# Connector_Board.net
KiCad netlist of a schematic drawn in EAGLE
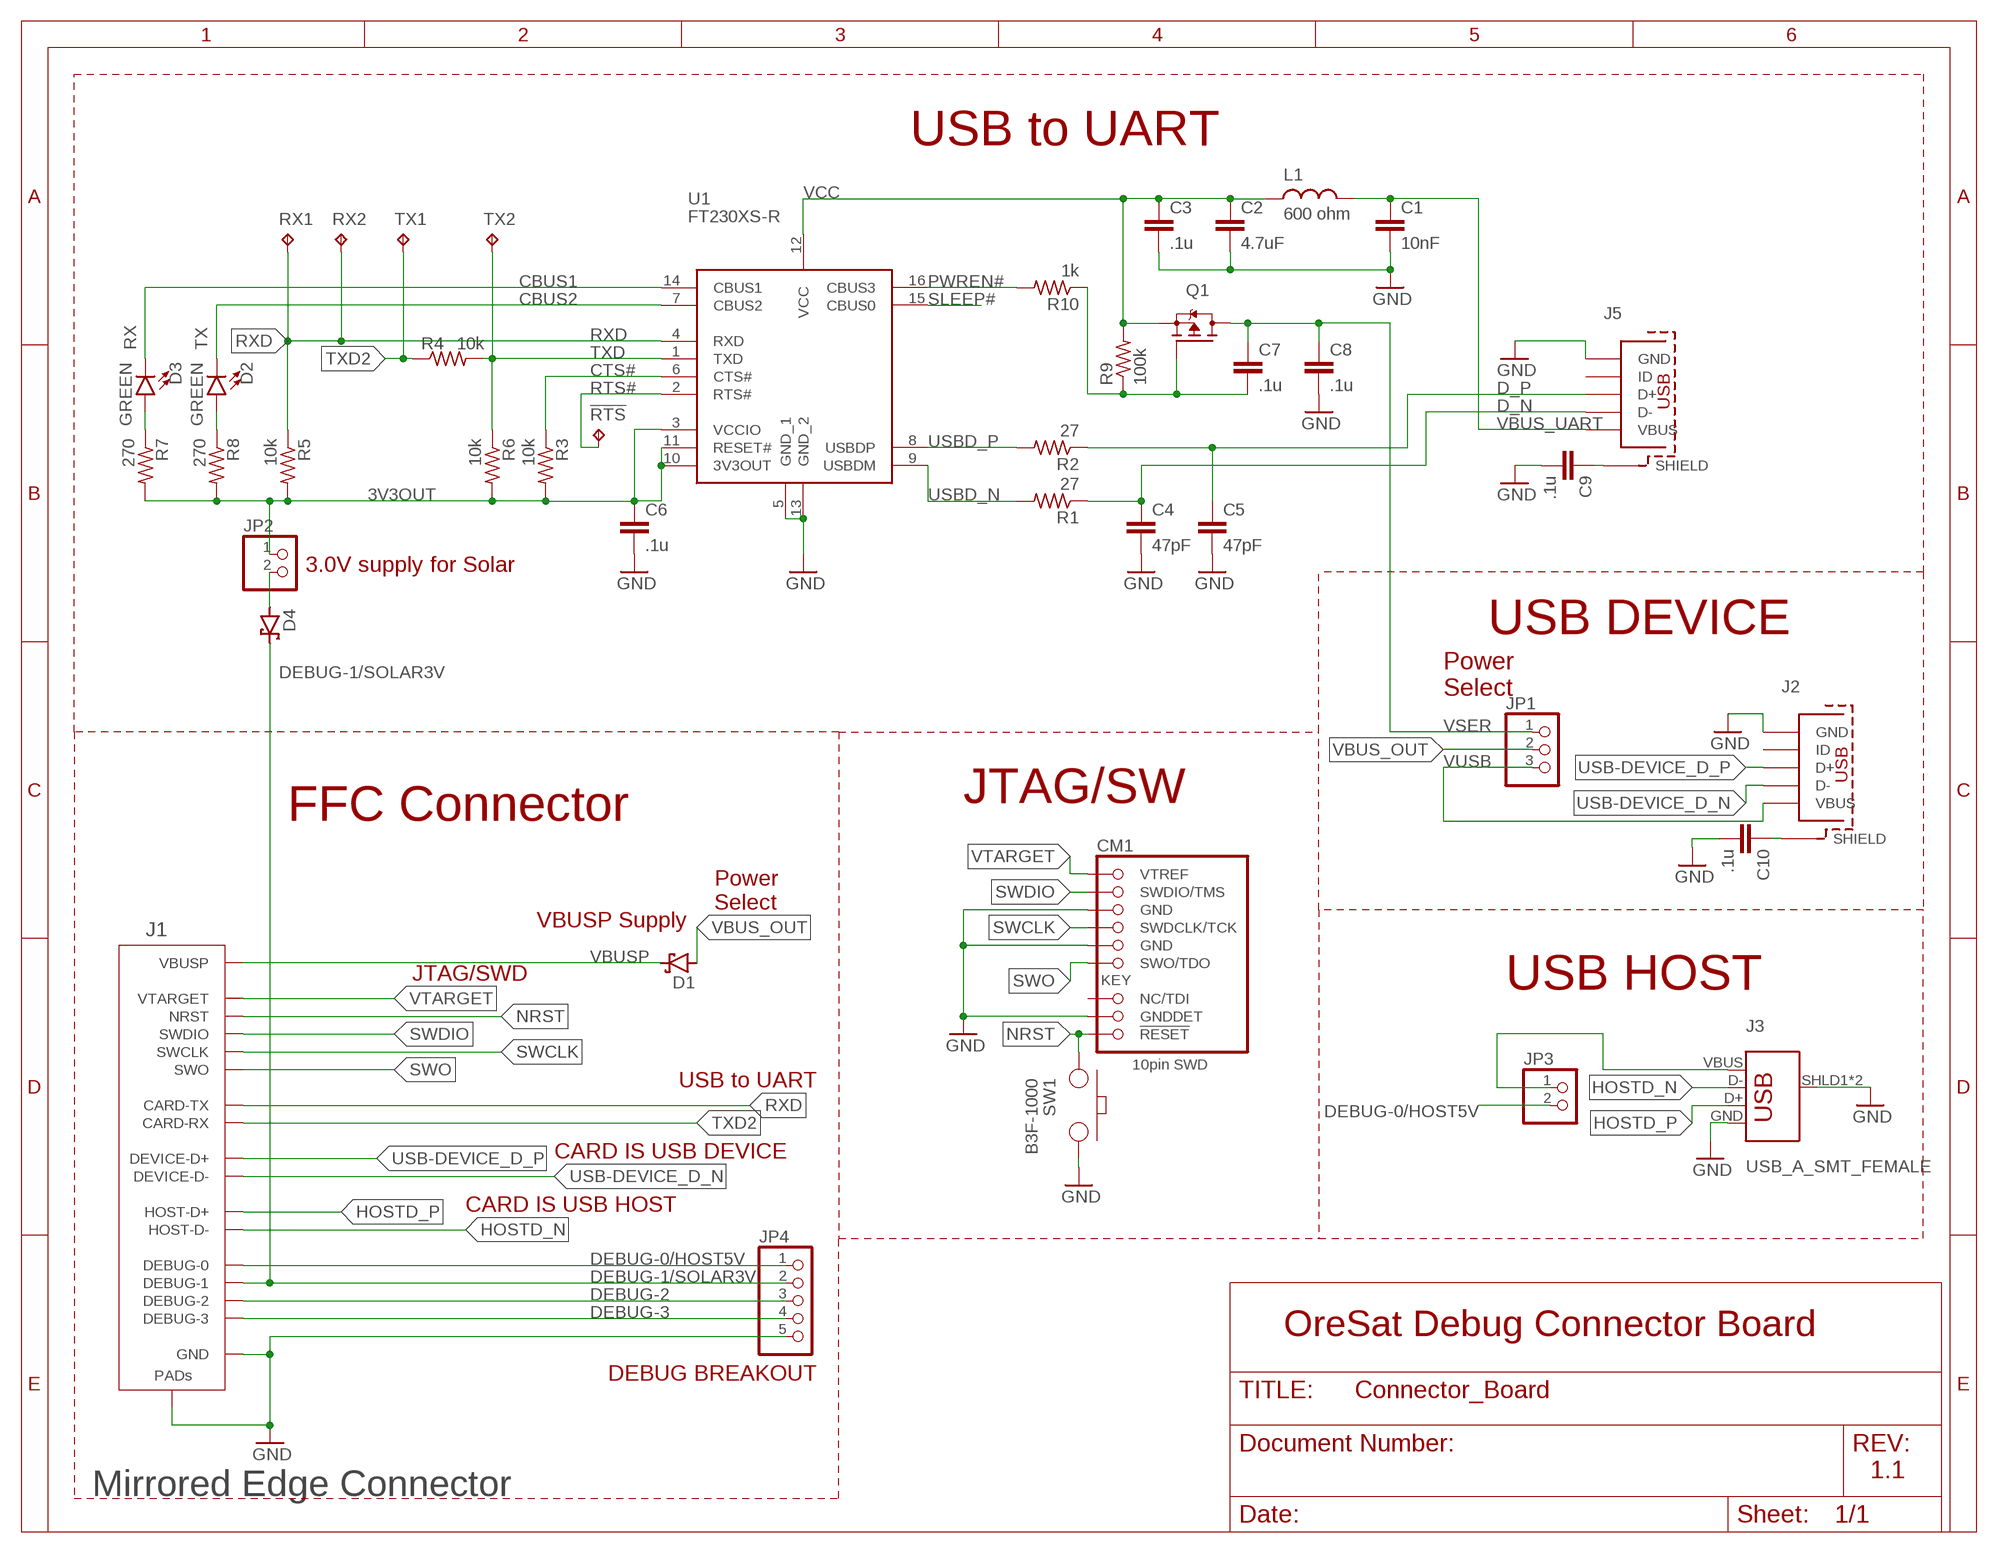
[diagram p0: schematic, sheet 1]

(export (version "E")
  (design (tool "Eeschema 10.0.6"))
  (components
    (comp (ref "!RTS")
      (value "TEST-POINT-LARGE")
      (footprint "eagle-import:1X01")
      (libsource (lib "eagle-import") (part "TEST-POINT-LARGE"))
    )
    (comp (ref "C1")
      (value "10nF")
      (footprint "eagle-import:.0603-C-NOSILK")
      (description "10000pF ±10% 50V Ceramic Capacitor X7R 0603 (1608 Metric)")
      (fields
        (field (name "DIGI-KEY_PART_NUMBER") "732-13185-1-ND")
        (field (name "MANUFACTURER") "Wurth Elektronik")
      )
      (libsource (lib "eagle-import") (part "C-EU0603-C-NOSILK"))
    )
    (comp (ref "C2")
      (value "4.7uF")
      (footprint "eagle-import:.0603-C-NOSILK")
      (description "4.7µF ±10% 10V Ceramic Capacitor X7S 0603 (1608 Metric)")
      (fields (field (name "DIGI-KEY_PART_NUMBER") "445-14258-1-ND") (field (name "MANUFACTURER") "TDK"))
      (libsource (lib "eagle-import") (part "C-EU0603-C-NOSILK"))
    )
    (comp (ref "C3")
      (value ".1u")
      (footprint "eagle-import:.0603-C-NOSILK")
      (description "0.1µF ±10% 10V Ceramic Capacitor X5R 0603 (1608 Metric)")
      (fields
        (field (name "DIGI-KEY_PART_NUMBER") "478-0603ZD104KAT2ACT-ND")
        (field (name "MANUFACTURER") "AVX")
      )
      (libsource (lib "eagle-import") (part "C-EU0603-C-NOSILK"))
    )
    (comp (ref "C4")
      (value "47pF")
      (footprint "eagle-import:.0603-C-NOSILK")
      (description "CAP CER 47PF 25V NP0 0603")
      (fields
        (field (name "DIGI-KEY_PART_NUMBER") "478-12679-1-ND")
        (field (name "MANUFACTURER") "AVX Corporation")
      )
      (libsource (lib "eagle-import") (part "C-EU0603-C-NOSILK"))
    )
    (comp (ref "C5")
      (value "47pF")
      (footprint "eagle-import:.0603-C-NOSILK")
      (description "CAP CER 47PF 25V NP0 0603")
      (fields
        (field (name "DIGI-KEY_PART_NUMBER") "478-12679-1-ND")
        (field (name "MANUFACTURER") "AVX Corporation")
      )
      (libsource (lib "eagle-import") (part "C-EU0603-C-NOSILK"))
    )
    (comp (ref "C6")
      (value ".1u")
      (footprint "eagle-import:.0603-C-NOSILK")
      (description "0.1µF ±10% 10V Ceramic Capacitor X5R 0603 (1608 Metric)")
      (fields
        (field (name "DIGI-KEY_PART_NUMBER") "478-0603ZD104KAT2ACT-ND")
        (field (name "MANUFACTURER") "AVX")
      )
      (libsource (lib "eagle-import") (part "C-EU0603-C-NOSILK"))
    )
    (comp (ref "C7")
      (value ".1u")
      (footprint "eagle-import:.0603-C-NOSILK")
      (description "0.1µF ±10% 10V Ceramic Capacitor X5R 0603 (1608 Metric)")
      (fields
        (field (name "DIGI-KEY_PART_NUMBER") "478-0603ZD104KAT2ACT-ND")
        (field (name "MANUFACTURER") "AVX")
      )
      (libsource (lib "eagle-import") (part "C-EU0603-C-NOSILK"))
    )
    (comp (ref "C8")
      (value ".1u")
      (footprint "eagle-import:.0603-C-NOSILK")
      (description "0.1µF ±10% 10V Ceramic Capacitor X5R 0603 (1608 Metric)")
      (fields
        (field (name "DIGI-KEY_PART_NUMBER") "478-0603ZD104KAT2ACT-ND")
        (field (name "MANUFACTURER") "AVX")
      )
      (libsource (lib "eagle-import") (part "C-EU0603-C-NOSILK"))
    )
    (comp (ref "C9")
      (value ".1u")
      (footprint "eagle-import:.0603-C-NOSILK")
      (description "0.1µF ±10% 10V Ceramic Capacitor X5R 0603 (1608 Metric)")
      (fields
        (field (name "DIGI-KEY_PART_NUMBER") "478-0603ZD104KAT2ACT-ND")
        (field (name "MANUFACTURER") "AVX")
      )
      (libsource (lib "eagle-import") (part "C-EU0603-C-NOSILK"))
    )
    (comp (ref "C10")
      (value ".1u")
      (footprint "eagle-import:.0603-C-NOSILK")
      (description "0.1µF ±10% 10V Ceramic Capacitor X5R 0603 (1608 Metric)")
      (fields
        (field (name "DIGI-KEY_PART_NUMBER") "478-0603ZD104KAT2ACT-ND")
        (field (name "MANUFACTURER") "AVX")
      )
      (libsource (lib "eagle-import") (part "C-EU0603-C-NOSILK"))
    )
    (comp (ref "CM1")
      (value "FTSH-105-XX-X-DV-K")
      (footprint "eagle-import:CON10_2X5_DUK_FTSH")
      (description "Connector Header Surface Mount 10 position 0.050\" (1.27mm)")
      (fields
        (field (name "DIGI-KEY_PART_NUMBER") "SAM13160CT-ND")
        (field (name "MANUFACTURER") "Samtec Inc.")
      )
      (libsource (lib "eagle-import") (part "FTSH-105-XX-X-DV-K"))
    )
    (comp (ref "D1")
      (value "CDBU0520")
      (footprint "eagle-import:DIOC1709X85N")
      (description "Diode Schottky 20V 500mA Surface Mount 0603/SOD-523F")
      (fields
        (field (name "DIGI-KEY_PART_NUMBER") "641-1332-1-ND")
        (field (name "MANUFACTURER") "Comchip Technology")
      )
      (libsource (lib "eagle-import") (part "CDBU0520"))
    )
    (comp (ref "D2")
      (value "GREEN")
      (footprint "eagle-import:LED-0603")
      (description "Green 573nm LED Indication - Discrete 2V 0603 (1608 Metric)")
      (fields
        (field (name "DIGI-KEY_PART_NUMBER") "732-12017-1-ND")
        (field (name "MANUFACTURER") "Würth Elektronik")
      )
      (libsource (lib "eagle-import") (part "LED-GREEN0603"))
    )
    (comp (ref "D3")
      (value "GREEN")
      (footprint "eagle-import:LED-0603")
      (description "Green 573nm LED Indication - Discrete 2V 0603 (1608 Metric)")
      (fields
        (field (name "DIGI-KEY_PART_NUMBER") "732-12017-1-ND")
        (field (name "MANUFACTURER") "Würth Elektronik")
      )
      (libsource (lib "eagle-import") (part "LED-GREEN0603"))
    )
    (comp (ref "D4")
      (value "CDBU0520")
      (footprint "eagle-import:DIOC1709X85N")
      (description "Diode Schottky 20V 500mA Surface Mount 0603/SOD-523F")
      (fields
        (field (name "DIGI-KEY_PART_NUMBER") "641-1332-1-ND")
        (field (name "MANUFACTURER") "Comchip Technology")
      )
      (libsource (lib "eagle-import") (part "CDBU0520"))
    )
    (comp (ref "J1")
      (value "ORESAT-DEBUG-CONNECTOR-MIRRORED-ALL")
      (footprint "eagle-import:TE_2-1734592-0")
      (description "20 Position FPC Connector Contacts, Bottom 0.020\" (0.50mm) Surface Mount, Right Angle")
      (fields
        (field (name "DIGI-KEY_PART_NUMBER") "A100287CT-ND")
        (field (name "MANUFACTURER") "TE Connectivity AMP Connectors")
      )
      (libsource (lib "eagle-import") (part "ORESAT-DEBUG-CONNECTOR-MIRRORED-ALL"))
    )
    (comp (ref "J2")
      (value "MICRO-USB-SOCKET")
      (footprint "eagle-import:629105136821")
      (description "CONN RCPT USB2.0 MICRO B SMD R/A")
      (fields
        (field (name "DIGI-KEY_PART_NUMBER") "732-3155-1-ND")
        (field (name "MANUFACTURER") "Würth Elektronik")
      )
      (libsource (lib "eagle-import") (part "MICRO-USB-SOCKET"))
    )
    (comp (ref "J3")
      (value "USB_A_SMT_FEMALE")
      (footprint "eagle-import:USB-A-S-SILK-FEMALE")
      (description "SparkFun Accessories USB Female Type A SMD Connector")
      (fields (field (name "MANUFACTURER") "SparkFun") (field (name "MANUFACTURER_PART_NUMBER") "PRT-09011"))
      (libsource (lib "eagle-import") (part "USB_A_SMT_FEMALE"))
    )
    (comp (ref "J5")
      (value "MICRO-USB-SOCKET")
      (footprint "eagle-import:629105136821")
      (description "CONN RCPT USB2.0 MICRO B SMD R/A")
      (fields
        (field (name "DIGI-KEY_PART_NUMBER") "732-3155-1-ND")
        (field (name "MANUFACTURER") "Würth Elektronik")
      )
      (libsource (lib "eagle-import") (part "MICRO-USB-SOCKET"))
    )
    (comp (ref "JP1")
      (value "PINHD-1X3")
      (footprint "eagle-import:1X03")
      (description "CONN HEADER VERT 3POS 2.54MM")
      (fields
        (field (name "DIGI-KEY_PART_NUMBER") "732-5316-ND")
        (field (name "MANUFACTURER") "Würth Elektronik")
      )
      (libsource (lib "eagle-import") (part "PINHD-1X3"))
    )
    (comp (ref "JP2")
      (value "PINHD-1X2")
      (footprint "eagle-import:1X02")
      (description "Connector Header Through Hole 2 position 0.100\" (2.54mm)")
      (fields
        (field (name "DIGI-KEY_PART_NUMBER") "732-5315-ND")
        (field (name "MANUFACTURER") "Würth Elektronik")
      )
      (libsource (lib "eagle-import") (part "PINHD-1X2"))
    )
    (comp (ref "JP3")
      (value "PINHD-1X2")
      (footprint "eagle-import:1X02")
      (description "Connector Header Through Hole 2 position 0.100\" (2.54mm)")
      (fields
        (field (name "DIGI-KEY_PART_NUMBER") "732-5315-ND")
        (field (name "MANUFACTURER") "Würth Elektronik")
      )
      (libsource (lib "eagle-import") (part "PINHD-1X2"))
    )
    (comp (ref "JP4")
      (value "PINHD-1X5")
      (footprint "eagle-import:1X05")
      (description "Connector Header Through Hole 5 position 0.100\" (2.54mm)")
      (fields
        (field (name "DIGI-KEY_PART_NUMBER") "732-5318-ND")
        (field (name "MANUFACTURER") "Würth Elektronik")
      )
      (libsource (lib "eagle-import") (part "PINHD-1X5"))
    )
    (comp (ref "L1")
      (value "600 ohm")
      (footprint "eagle-import:.0805-A-NOSILK")
      (description "FERRITE BEAD 600 OHM 0805 1LN")
      (fields
        (field (name "DIGI-KEY_PART_NUMBER") "240-2390-1-ND")
        (field (name "MANUFACTURER") "Laird-Signal Integrity Products")
      )
      (libsource (lib "eagle-import") (part "L-US0805-A-NOSILK"))
    )
    (comp (ref "Q1")
      (value "MOSFET-PCH-SOT23-6")
      (footprint "eagle-import:SOT23-6")
      (description "P-Channel 30V 4.1A 350mW Surface Mount SOT-23-6L")
      (fields
        (field (name "DIGI-KEY_PART_NUMBER") "SIL3407-TPMSCT-ND")
        (field (name "MANUFACTURER") "Micro Commercial Co")
      )
      (libsource (lib "eagle-import") (part "MOSFET-PCH-SOT23-6"))
    )
    (comp (ref "R1")
      (value "27")
      (footprint "eagle-import:.0603-C-NOSILK")
      (description "RES SMD 27 OHM 1% 1/10W 0603")
      (fields
        (field (name "DIGI-KEY_PART_NUMBER") "CR0603-FX-27R0ELFCT-ND")
        (field (name "MANUFACTURER") "Bourns Inc.")
      )
      (libsource (lib "eagle-import") (part "R-US_0603-C-NOSILK"))
    )
    (comp (ref "R2")
      (value "27")
      (footprint "eagle-import:.0603-C-NOSILK")
      (description "RES SMD 27 OHM 1% 1/10W 0603")
      (fields
        (field (name "DIGI-KEY_PART_NUMBER") "CR0603-FX-27R0ELFCT-ND")
        (field (name "MANUFACTURER") "Bourns Inc.")
      )
      (libsource (lib "eagle-import") (part "R-US_0603-C-NOSILK"))
    )
    (comp (ref "R3")
      (value "10k")
      (footprint "eagle-import:.0603-C-NOSILK")
      (description "10 kOhms ±1% 0.1W, 1/10W Chip Resistor 0603 (1608 Metric) Moisture Resistant Thick Film")
      (fields
        (field (name "DIGI-KEY_PART_NUMBER") "CR0603-FX-1002ELFCT-ND")
        (field (name "MANUFACTURER") "Bourns")
      )
      (libsource (lib "eagle-import") (part "R-US_0603-C-NOSILK"))
    )
    (comp (ref "R4")
      (value "10k")
      (footprint "eagle-import:.0603-C-NOSILK")
      (description "10 kOhms ±1% 0.1W, 1/10W Chip Resistor 0603 (1608 Metric) Moisture Resistant Thick Film")
      (fields
        (field (name "DIGI-KEY_PART_NUMBER") "CR0603-FX-1002ELFCT-ND")
        (field (name "MANUFACTURER") "Bourns")
      )
      (libsource (lib "eagle-import") (part "R-US_0603-C-NOSILK"))
    )
    (comp (ref "R5")
      (value "10k")
      (footprint "eagle-import:.0603-C-NOSILK")
      (description "10 kOhms ±1% 0.1W, 1/10W Chip Resistor 0603 (1608 Metric) Moisture Resistant Thick Film")
      (fields
        (field (name "DIGI-KEY_PART_NUMBER") "CR0603-FX-1002ELFCT-ND")
        (field (name "MANUFACTURER") "Bourns")
      )
      (libsource (lib "eagle-import") (part "R-US_0603-C-NOSILK"))
    )
    (comp (ref "R6")
      (value "10k")
      (footprint "eagle-import:.0603-C-NOSILK")
      (description "10 kOhms ±1% 0.1W, 1/10W Chip Resistor 0603 (1608 Metric) Moisture Resistant Thick Film")
      (fields
        (field (name "DIGI-KEY_PART_NUMBER") "CR0603-FX-1002ELFCT-ND")
        (field (name "MANUFACTURER") "Bourns")
      )
      (libsource (lib "eagle-import") (part "R-US_0603-C-NOSILK"))
    )
    (comp (ref "R7")
      (value "270")
      (footprint "eagle-import:.0603-C-NOSILK")
      (description "RES SMD 270 OHM 1% 1/10W 0603")
      (fields
        (field (name "DIGI-KEY_PART_NUMBER") "P270HCT-ND")
        (field (name "MANUFACTURER") "Panasonic Electronic Components")
      )
      (libsource (lib "eagle-import") (part "R-US_0603-C-NOSILK"))
    )
    (comp (ref "R8")
      (value "270")
      (footprint "eagle-import:.0603-C-NOSILK")
      (description "RES SMD 270 OHM 1% 1/10W 0603")
      (fields
        (field (name "DIGI-KEY_PART_NUMBER") "P270HCT-ND")
        (field (name "MANUFACTURER") "Panasonic Electronic Components")
      )
      (libsource (lib "eagle-import") (part "R-US_0603-C-NOSILK"))
    )
    (comp (ref "R9")
      (value "100k")
      (footprint "eagle-import:.0603-C-NOSILK")
      (description "100 kOhms ±5% 0.1W, 1/10W Chip Resistor 0603 (1608 Metric) Automotive AEC-Q200 Thick Film")
      (fields
        (field (name "DIGI-KEY_PART_NUMBER") "RMCF0603JG100KTR-ND")
        (field (name "MANUFACTURER") "Stackpole Electronics Inc")
      )
      (libsource (lib "eagle-import") (part "R-US_0603-C-NOSILK"))
    )
    (comp (ref "R10")
      (value "1k")
      (footprint "eagle-import:.0603-C-NOSILK")
      (description "RES SMD 1K OHM 1% 1/10W 0603")
      (fields (field (name "DIGI-KEY_PART_NUMBER") "311-1.00KHRCT-ND") (field (name "MANUFACTURER") "Yageo"))
      (libsource (lib "eagle-import") (part "R-US_0603-C-NOSILK"))
    )
    (comp (ref "RX1")
      (value "TEST-POINT-LARGE")
      (footprint "eagle-import:1X01")
      (libsource (lib "eagle-import") (part "TEST-POINT-LARGE"))
    )
    (comp (ref "RX2")
      (value "TEST-POINT-LARGE")
      (footprint "eagle-import:1X01")
      (libsource (lib "eagle-import") (part "TEST-POINT-LARGE"))
    )
    (comp (ref "SW1")
      (value "B3F-1000")
      (footprint "eagle-import:SW-MOM-OMRON-6X6X4.3")
      (description "SWITCH TACTILE SPST-NO 0.05A 24V")
      (fields
        (field (name "DIGI-KEY_PART_NUMBER") "SW400-ND")
        (field (name "MANUFACTURER") "Omron Electronics Inc-EMC Div")
      )
      (libsource (lib "eagle-import") (part "SW-MOM-TACTILE-B3F-1000"))
    )
    (comp (ref "TX1")
      (value "TEST-POINT-LARGE")
      (footprint "eagle-import:1X01")
      (libsource (lib "eagle-import") (part "TEST-POINT-LARGE"))
    )
    (comp (ref "TX2")
      (value "TEST-POINT-LARGE")
      (footprint "eagle-import:1X01")
      (libsource (lib "eagle-import") (part "TEST-POINT-LARGE"))
    )
    (comp (ref "U1")
      (value "FT230XS-R")
      (footprint "eagle-import:SOP64P599X175-16N")
      (fields
        (field (name "MANUFACTURER") "FTDI Chip")
        (field (name "MOUSER_PART_NUMBER") "895-FT230XS-R")
        (field (name "DIGI-KEY_PART_NUMBER") "768-1135-1-ND")
      )
      (libsource (lib "eagle-import") (part "FT230XS-R"))
    )
  )
  (nets
    (net (code "1") (name "/3V3OUT") (class "Default")
      (node (ref "C6") (pin "1") (pinfunction "1_1") (pintype "passive"))
      (node (ref "JP2") (pin "1") (pinfunction "1_1") (pintype "passive"))
      (node (ref "R3") (pin "2") (pinfunction "2_2") (pintype "passive"))
      (node (ref "R5") (pin "2") (pinfunction "2_2") (pintype "passive"))
      (node (ref "R6") (pin "2") (pinfunction "2_2") (pintype "passive"))
      (node (ref "R7") (pin "2") (pinfunction "2_2") (pintype "passive"))
      (node (ref "R8") (pin "2") (pinfunction "2_2") (pintype "passive"))
      (node (ref "U1") (pin "10") (pinfunction "3V3OUT_10") (pintype "output"))
      (node (ref "U1") (pin "11") (pinfunction "RESET#_11") (pintype "bidirectional"))
      (node (ref "U1") (pin "3") (pinfunction "VCCIO_3") (pintype "power_in"))
    )
    (net (code "2") (name "/CBUS1") (class "Default")
      (node (ref "D3") (pin "C") (pinfunction "C_C") (pintype "passive"))
      (node (ref "U1") (pin "14") (pinfunction "CBUS1_14") (pintype "bidirectional"))
    )
    (net (code "3") (name "/CBUS2") (class "Default")
      (node (ref "D2") (pin "C") (pinfunction "C_C") (pintype "passive"))
      (node (ref "U1") (pin "7") (pinfunction "CBUS2_7") (pintype "bidirectional"))
    )
    (net (code "4") (name "/CTS#") (class "Default")
      (node (ref "R3") (pin "1") (pinfunction "1_1") (pintype "passive"))
      (node (ref "U1") (pin "6") (pinfunction "CTS#_6") (pintype "bidirectional"))
    )
    (net (code "5") (name "/DEBUG-0{slash}HOST5V") (class "Default")
      (node (ref "J1") (pin "4") (pinfunction "DEBUG-0_4") (pintype "passive"))
      (node (ref "JP3") (pin "2") (pinfunction "2_2") (pintype "passive"))
      (node (ref "JP4") (pin "1") (pinfunction "1_1") (pintype "passive"))
    )
    (net (code "6") (name "/DEBUG-1{slash}SOLAR3V") (class "Default")
      (node (ref "D4") (pin "1") (pinfunction "C_1") (pintype "passive"))
      (node (ref "J1") (pin "3") (pinfunction "DEBUG-1_3") (pintype "passive"))
      (node (ref "JP4") (pin "2") (pinfunction "2_2") (pintype "passive"))
    )
    (net (code "7") (name "/DEBUG-2") (class "Default")
      (node (ref "J1") (pin "2") (pinfunction "DEBUG-2_2") (pintype "passive"))
      (node (ref "JP4") (pin "3") (pinfunction "3_3") (pintype "passive"))
    )
    (net (code "8") (name "/DEBUG-3") (class "Default")
      (node (ref "J1") (pin "1") (pinfunction "DEBUG-3_1") (pintype "passive"))
      (node (ref "JP4") (pin "4") (pinfunction "4_4") (pintype "passive"))
    )
    (net (code "9") (name "/D_N") (class "Default")
      (node (ref "C4") (pin "1") (pinfunction "1_1") (pintype "passive"))
      (node (ref "J5") (pin "2") (pinfunction "D-_2") (pintype "passive"))
      (node (ref "R1") (pin "1") (pinfunction "1_1") (pintype "passive"))
    )
    (net (code "10") (name "/D_P") (class "Default")
      (node (ref "C5") (pin "1") (pinfunction "1_1") (pintype "passive"))
      (node (ref "J5") (pin "3") (pinfunction "D+_3") (pintype "passive"))
      (node (ref "R2") (pin "1") (pinfunction "1_1") (pintype "passive"))
    )
    (net (code "11") (name "/PWREN#") (class "Default")
      (node (ref "R10") (pin "2") (pinfunction "2_2") (pintype "passive"))
      (node (ref "U1") (pin "16") (pinfunction "CBUS3_16") (pintype "bidirectional"))
    )
    (net (code "12") (name "/RTS#") (class "Default")
      (node (ref "!RTS") (pin "1") (pinfunction "TP_1") (pintype "input"))
      (node (ref "U1") (pin "2") (pinfunction "RTS#_2") (pintype "bidirectional"))
    )
    (net (code "13") (name "/SLEEP#") (class "Default")
      (node (ref "U1") (pin "15") (pinfunction "CBUS0_15") (pintype "bidirectional"))
    )
    (net (code "14") (name "/TXD") (class "Default")
      (node (ref "R4") (pin "2") (pinfunction "2_2") (pintype "passive"))
      (node (ref "R6") (pin "1") (pinfunction "1_1") (pintype "passive"))
      (node (ref "TX2") (pin "1") (pinfunction "TP_1") (pintype "input"))
      (node (ref "U1") (pin "1") (pinfunction "TXD_1") (pintype "bidirectional"))
    )
    (net (code "15") (name "/USBD_N") (class "Default")
      (node (ref "R1") (pin "2") (pinfunction "2_2") (pintype "passive"))
      (node (ref "U1") (pin "9") (pinfunction "USBDM_9") (pintype "bidirectional"))
    )
    (net (code "16") (name "/USBD_P") (class "Default")
      (node (ref "R2") (pin "2") (pinfunction "2_2") (pintype "passive"))
      (node (ref "U1") (pin "8") (pinfunction "USBDP_8") (pintype "bidirectional"))
    )
    (net (code "17") (name "/VBUSP") (class "Default")
      (node (ref "D1") (pin "1") (pinfunction "C_1") (pintype "passive"))
      (node (ref "J1") (pin "19") (pinfunction "VBUSP_19") (pintype "passive"))
      (node (ref "J1") (pin "20") (pinfunction "VBUSP_20") (pintype "passive"))
    )
    (net (code "18") (name "/VBUS_UART") (class "Default")
      (node (ref "C1") (pin "1") (pinfunction "1_1") (pintype "passive"))
      (node (ref "J5") (pin "1") (pinfunction "VBUS_1") (pintype "passive"))
      (node (ref "L1") (pin "2") (pinfunction "2_2") (pintype "passive"))
    )
    (net (code "19") (name "/VCC") (class "Default")
      (node (ref "C2") (pin "1") (pinfunction "1_1") (pintype "passive"))
      (node (ref "C3") (pin "1") (pinfunction "1_1") (pintype "passive"))
      (node (ref "L1") (pin "1") (pinfunction "1_1") (pintype "passive"))
      (node (ref "Q1") (pin "4") (pinfunction "S_4") (pintype "passive"))
      (node (ref "R9") (pin "2") (pinfunction "2_2") (pintype "passive"))
      (node (ref "U1") (pin "12") (pinfunction "VCC_12") (pintype "power_in"))
    )
    (net (code "20") (name "/VSER") (class "Default")
      (node (ref "C7") (pin "1") (pinfunction "1_1") (pintype "passive"))
      (node (ref "C8") (pin "1") (pinfunction "1_1") (pintype "passive"))
      (node (ref "JP1") (pin "1") (pinfunction "1_1") (pintype "passive"))
      (node (ref "Q1") (pin "1") (pinfunction "D_1") (pintype "passive"))
      (node (ref "Q1") (pin "2") (pinfunction "D_2") (pintype "passive"))
      (node (ref "Q1") (pin "5") (pinfunction "D_5") (pintype "passive"))
      (node (ref "Q1") (pin "6") (pinfunction "D_6") (pintype "passive"))
    )
    (net (code "21") (name "/VUSB") (class "Default")
      (node (ref "J2") (pin "1") (pinfunction "VBUS_1") (pintype "passive"))
      (node (ref "JP1") (pin "3") (pinfunction "3_3") (pintype "passive"))
    )
    (net (code "22") (name "GND") (class "Default")
      (node (ref "C1") (pin "2") (pinfunction "2_2") (pintype "passive"))
      (node (ref "C10") (pin "2") (pinfunction "2_2") (pintype "passive"))
      (node (ref "C2") (pin "2") (pinfunction "2_2") (pintype "passive"))
      (node (ref "C3") (pin "2") (pinfunction "2_2") (pintype "passive"))
      (node (ref "C4") (pin "2") (pinfunction "2_2") (pintype "passive"))
      (node (ref "C5") (pin "2") (pinfunction "2_2") (pintype "passive"))
      (node (ref "C6") (pin "2") (pinfunction "2_2") (pintype "passive"))
      (node (ref "C8") (pin "2") (pinfunction "2_2") (pintype "passive"))
      (node (ref "C9") (pin "2") (pinfunction "2_2") (pintype "passive"))
      (node (ref "CM1") (pin "3") (pinfunction "GND_3") (pintype "passive"))
      (node (ref "CM1") (pin "5") (pinfunction "GND_5") (pintype "passive"))
      (node (ref "CM1") (pin "9") (pinfunction "GNDDET_9") (pintype "passive"))
      (node (ref "J1") (pin "12") (pinfunction "GND_12") (pintype "passive"))
      (node (ref "J1") (pin "15") (pinfunction "GND_15") (pintype "passive"))
      (node (ref "J1") (pin "18") (pinfunction "GND_18") (pintype "passive"))
      (node (ref "J1") (pin "PAD1") (pinfunction "PAD_PAD1") (pintype "bidirectional"))
      (node (ref "J1") (pin "PAD2") (pinfunction "PAD_PAD2") (pintype "bidirectional"))
      (node (ref "J2") (pin "5") (pinfunction "GND_5") (pintype "passive"))
      (node (ref "J3") (pin "GND") (pinfunction "GND_GND") (pintype "power_in"))
      (node (ref "J3") (pin "SHLD1") (pinfunction "SHIELD_SHLD1") (pintype "bidirectional"))
      (node (ref "J3") (pin "SHLD2") (pinfunction "SHIELD_SHLD2") (pintype "bidirectional"))
      (node (ref "J5") (pin "5") (pinfunction "GND_5") (pintype "passive"))
      (node (ref "JP4") (pin "5") (pinfunction "5_5") (pintype "passive"))
      (node (ref "SW1") (pin "3") (pinfunction "2_3") (pintype "passive"))
      (node (ref "SW1") (pin "4") (pinfunction "2_4") (pintype "passive"))
      (node (ref "U1") (pin "13") (pinfunction "GND_2_13") (pintype "power_in"))
      (node (ref "U1") (pin "5") (pinfunction "GND_1_5") (pintype "power_in"))
    )
    (net (code "23") (name "HOSTD_N") (class "Default")
      (node (ref "J1") (pin "13") (pinfunction "HOST-D-_13") (pintype "passive"))
      (node (ref "J3") (pin "D-") (pinfunction "D-_D-") (pintype "bidirectional"))
    )
    (net (code "24") (name "HOSTD_P") (class "Default")
      (node (ref "J1") (pin "14") (pinfunction "HOST-D+_14") (pintype "passive"))
      (node (ref "J3") (pin "D+") (pinfunction "D+_D+") (pintype "bidirectional"))
    )
    (net (code "25") (name "NRST") (class "Default")
      (node (ref "CM1") (pin "10") (pinfunction "~{RESET}_10") (pintype "passive"))
      (node (ref "J1") (pin "11") (pinfunction "NRST_11") (pintype "passive"))
      (node (ref "SW1") (pin "1") (pinfunction "1_1") (pintype "passive"))
      (node (ref "SW1") (pin "2") (pinfunction "1_2") (pintype "passive"))
    )
    (net (code "26") (name "Net-(C9-Pad1)") (class "Default")
      (node (ref "C9") (pin "1") (pinfunction "1_1") (pintype "passive"))
      (node (ref "J5") (pin "SHELL") (pinfunction "SHIELD_SHELL") (pintype "passive"))
      (node (ref "J5") (pin "SHELL1") (pinfunction "SHIELD_SHELL1") (pintype "passive"))
      (node (ref "J5") (pin "SHELL2") (pinfunction "SHIELD_SHELL2") (pintype "passive"))
      (node (ref "J5") (pin "SHELL3") (pinfunction "SHIELD_SHELL3") (pintype "passive"))
    )
    (net (code "27") (name "Net-(C10-Pad1)") (class "Default")
      (node (ref "C10") (pin "1") (pinfunction "1_1") (pintype "passive"))
      (node (ref "J2") (pin "SHELL") (pinfunction "SHIELD_SHELL") (pintype "passive"))
      (node (ref "J2") (pin "SHELL1") (pinfunction "SHIELD_SHELL1") (pintype "passive"))
      (node (ref "J2") (pin "SHELL2") (pinfunction "SHIELD_SHELL2") (pintype "passive"))
      (node (ref "J2") (pin "SHELL3") (pinfunction "SHIELD_SHELL3") (pintype "passive"))
    )
    (net (code "28") (name "Net-(D2-PadA)") (class "Default")
      (node (ref "D2") (pin "A") (pinfunction "A_A") (pintype "passive"))
      (node (ref "R8") (pin "1") (pinfunction "1_1") (pintype "passive"))
    )
    (net (code "29") (name "Net-(D3-PadA)") (class "Default")
      (node (ref "D3") (pin "A") (pinfunction "A_A") (pintype "passive"))
      (node (ref "R7") (pin "1") (pinfunction "1_1") (pintype "passive"))
    )
    (net (code "30") (name "Net-(D4-A)") (class "Default")
      (node (ref "D4") (pin "2") (pinfunction "A_2") (pintype "passive"))
      (node (ref "JP2") (pin "2") (pinfunction "2_2") (pintype "passive"))
    )
    (net (code "31") (name "Net-(J3-PadVBUS)") (class "Default")
      (node (ref "J3") (pin "VBUS") (pinfunction "VBUS_VBUS") (pintype "power_in"))
      (node (ref "JP3") (pin "1") (pinfunction "1_1") (pintype "passive"))
    )
    (net (code "32") (name "Net-(Q1-G)") (class "Default")
      (node (ref "C7") (pin "2") (pinfunction "2_2") (pintype "passive"))
      (node (ref "Q1") (pin "3") (pinfunction "G_3") (pintype "passive"))
      (node (ref "R10") (pin "1") (pinfunction "1_1") (pintype "passive"))
      (node (ref "R9") (pin "1") (pinfunction "1_1") (pintype "passive"))
    )
    (net (code "33") (name "RXD") (class "Default")
      (node (ref "J1") (pin "8") (pinfunction "CARD-TX_8") (pintype "passive"))
      (node (ref "R5") (pin "1") (pinfunction "1_1") (pintype "passive"))
      (node (ref "RX1") (pin "1") (pinfunction "TP_1") (pintype "input"))
      (node (ref "RX2") (pin "1") (pinfunction "TP_1") (pintype "input"))
      (node (ref "U1") (pin "4") (pinfunction "RXD_4") (pintype "bidirectional"))
    )
    (net (code "34") (name "SWCLK") (class "Default")
      (node (ref "CM1") (pin "4") (pinfunction "SWDCLK/TCK_4") (pintype "passive"))
      (node (ref "J1") (pin "6") (pinfunction "SWCLK_6") (pintype "passive"))
    )
    (net (code "35") (name "SWDIO") (class "Default")
      (node (ref "CM1") (pin "2") (pinfunction "SWDIO/TMS_2") (pintype "passive"))
      (node (ref "J1") (pin "7") (pinfunction "SWDIO_7") (pintype "passive"))
    )
    (net (code "36") (name "SWO") (class "Default")
      (node (ref "CM1") (pin "6") (pinfunction "SWO/TDO_6") (pintype "passive"))
      (node (ref "J1") (pin "5") (pinfunction "SWO_5") (pintype "passive"))
    )
    (net (code "37") (name "TXD2") (class "Default")
      (node (ref "J1") (pin "9") (pinfunction "CARD-RX_9") (pintype "passive"))
      (node (ref "R4") (pin "1") (pinfunction "1_1") (pintype "passive"))
      (node (ref "TX1") (pin "1") (pinfunction "TP_1") (pintype "input"))
    )
    (net (code "38") (name "USB-DEVICE_D_N") (class "Default")
      (node (ref "J1") (pin "16") (pinfunction "DEVICE-D-_16") (pintype "passive"))
      (node (ref "J2") (pin "2") (pinfunction "D-_2") (pintype "passive"))
    )
    (net (code "39") (name "USB-DEVICE_D_P") (class "Default")
      (node (ref "J1") (pin "17") (pinfunction "DEVICE-D+_17") (pintype "passive"))
      (node (ref "J2") (pin "3") (pinfunction "D+_3") (pintype "passive"))
    )
    (net (code "40") (name "VBUS_OUT") (class "Default")
      (node (ref "D1") (pin "2") (pinfunction "A_2") (pintype "passive"))
      (node (ref "JP1") (pin "2") (pinfunction "2_2") (pintype "passive"))
    )
    (net (code "41") (name "VTARGET") (class "Default")
      (node (ref "CM1") (pin "1") (pinfunction "VTREF_1") (pintype "passive"))
      (node (ref "J1") (pin "10") (pinfunction "VTARGET_10") (pintype "passive"))
    )
    (net (code "42") (name "unconnected-(CM1-NC{slash}TDI-Pad8)") (class "Default")
      (node (ref "CM1") (pin "8") (pinfunction "NC/TDI_8") (pintype "passive"))
    )
    (net (code "43") (name "unconnected-(J2-ID-Pad4)") (class "Default")
      (node (ref "J2") (pin "4") (pinfunction "ID_4") (pintype "passive"))
    )
    (net (code "44") (name "unconnected-(J5-ID-Pad4)") (class "Default")
      (node (ref "J5") (pin "4") (pinfunction "ID_4") (pintype "passive"))
    )
  )
)
